# first_light.net
KiCad netlist of a schematic drawn in EAGLE
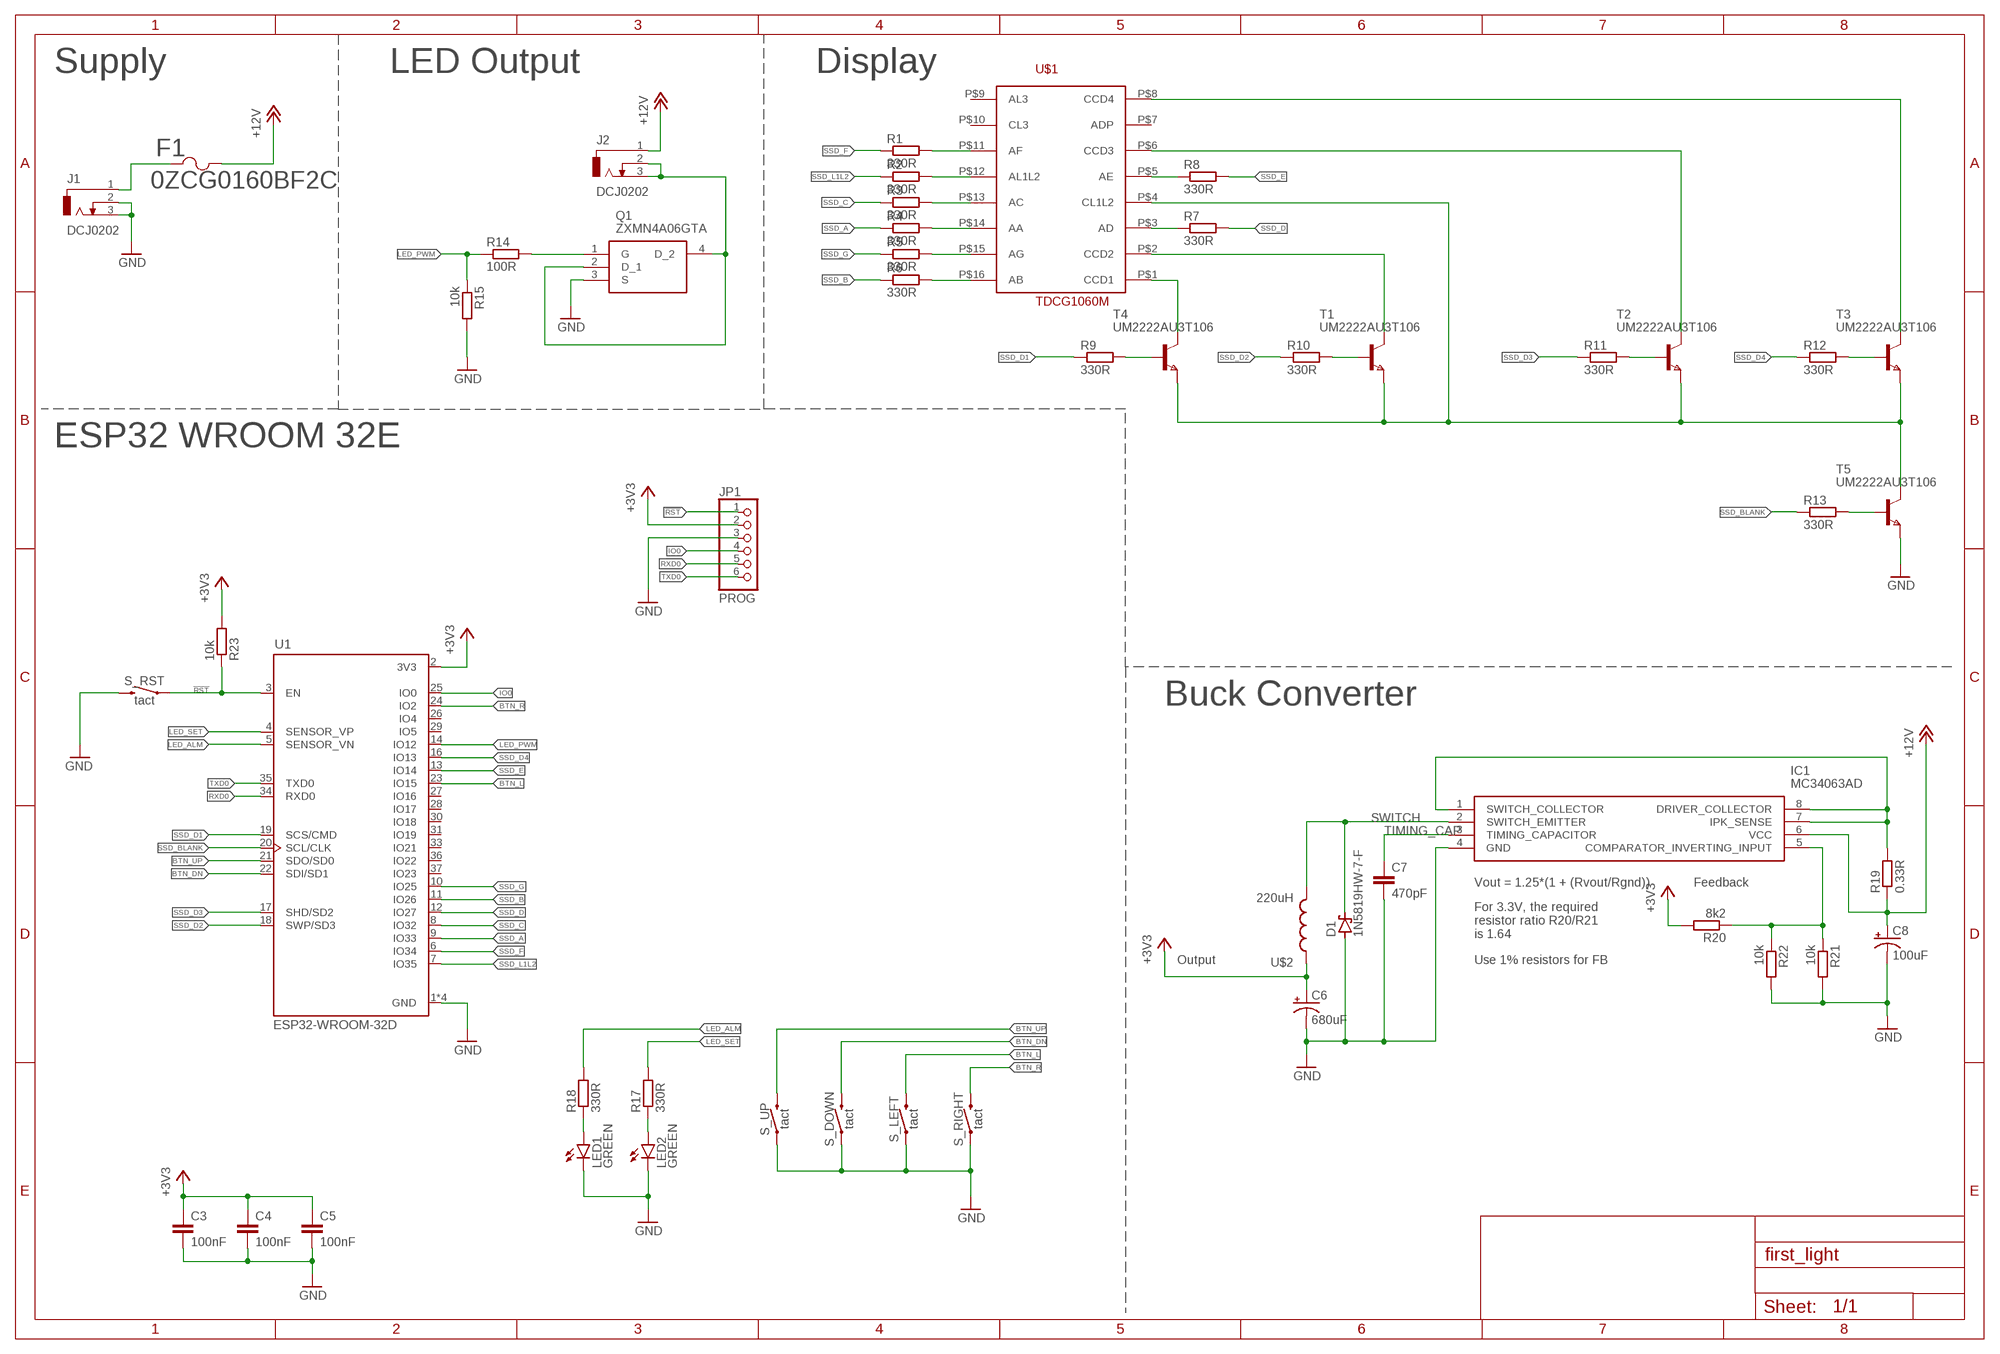
[diagram p0: schematic, sheet 1]

(export (version "E")
  (design (tool "Eeschema 10.0.6"))
  (components
    (comp (ref "C3")
      (value "100nF")
      (footprint "eagle-import:C0603")
      (libsource (lib "eagle-import") (part "C-EUC0603"))
    )
    (comp (ref "C4")
      (value "100nF")
      (footprint "eagle-import:C0603")
      (libsource (lib "eagle-import") (part "C-EUC0603"))
    )
    (comp (ref "C5")
      (value "100nF")
      (footprint "eagle-import:C0603")
      (libsource (lib "eagle-import") (part "C-EUC0603"))
    )
    (comp (ref "C6")
      (value "680uF")
      (footprint "eagle-import:153CLV-0605")
      (libsource (lib "eagle-import") (part "CPOL-US153CLV-0605"))
    )
    (comp (ref "C7")
      (value "470pF")
      (footprint "eagle-import:C0603")
      (libsource (lib "eagle-import") (part "rcl_334_C-EUC0603"))
    )
    (comp (ref "C8")
      (value "100uF")
      (footprint "eagle-import:153CLV-0605")
      (libsource (lib "eagle-import") (part "CPOL-US153CLV-0605"))
    )
    (comp (ref "D1")
      (value "SCHOTTKY-1N5819HW-7-F")
      (footprint "eagle-import:SOD123")
      (libsource (lib "eagle-import") (part "SCHOTTKY-1N5819HW-7-F"))
    )
    (comp (ref "F1")
      (value "0ZCG0160BF2C")
      (footprint "eagle-import:0ZCG_BEL")
      (fields (field (name "COPYRIGHT") "Copyright (C) 2021 Ultra Librarian. All rights reserved."))
      (libsource (lib "eagle-import") (part "0ZCG0160BF2C"))
    )
    (comp (ref "IC1")
      (value "MC34063AD")
      (footprint "eagle-import:SOIC127P600X175-8N")
      (fields (field (name "MOUSER_PART_NUMBER") "512-MC34063AD"))
      (libsource (lib "eagle-import") (part "MC34063AD"))
    )
    (comp (ref "J1")
      (value "DCJ0202")
      (footprint "eagle-import:DCJ0202")
      (libsource (lib "eagle-import") (part "DCJ0202"))
    )
    (comp (ref "J2")
      (value "DCJ0202")
      (footprint "eagle-import:DCJ0202")
      (libsource (lib "eagle-import") (part "DCJ0202"))
    )
    (comp (ref "JP1")
      (value "PROG")
      (footprint "eagle-import:1X06")
      (libsource (lib "eagle-import") (part "PINHD-1X6"))
    )
    (comp (ref "LED1")
      (value "GREEN")
      (footprint "eagle-import:CHIP-LED0603")
      (libsource (lib "eagle-import") (part "LEDCHIP-LED0603"))
    )
    (comp (ref "LED2")
      (value "GREEN")
      (footprint "eagle-import:CHIP-LED0603")
      (libsource (lib "eagle-import") (part "LEDCHIP-LED0603"))
    )
    (comp (ref "Q1")
      (value "ZXMN4A06GTA")
      (footprint "eagle-import:SOT230P700X180-4N")
      (fields (field (name "MOUSER_PART_NUMBER") "522-ZXMN4A06GTA"))
      (libsource (lib "eagle-import") (part "ZXMN4A06GTA"))
    )
    (comp (ref "R1")
      (value "330R")
      (footprint "eagle-import:R0603")
      (libsource (lib "eagle-import") (part "R-EU_R0603"))
    )
    (comp (ref "R2")
      (value "330R")
      (footprint "eagle-import:R0603")
      (libsource (lib "eagle-import") (part "R-EU_R0603"))
    )
    (comp (ref "R3")
      (value "330R")
      (footprint "eagle-import:R0603")
      (libsource (lib "eagle-import") (part "R-EU_R0603"))
    )
    (comp (ref "R4")
      (value "330R")
      (footprint "eagle-import:R0603")
      (libsource (lib "eagle-import") (part "R-EU_R0603"))
    )
    (comp (ref "R5")
      (value "330R")
      (footprint "eagle-import:R0603")
      (libsource (lib "eagle-import") (part "R-EU_R0603"))
    )
    (comp (ref "R6")
      (value "330R")
      (footprint "eagle-import:R0603")
      (libsource (lib "eagle-import") (part "R-EU_R0603"))
    )
    (comp (ref "R7")
      (value "330R")
      (footprint "eagle-import:R0603")
      (libsource (lib "eagle-import") (part "R-EU_R0603"))
    )
    (comp (ref "R8")
      (value "330R")
      (footprint "eagle-import:R0603")
      (libsource (lib "eagle-import") (part "R-EU_R0603"))
    )
    (comp (ref "R9")
      (value "330R")
      (footprint "eagle-import:R0603")
      (libsource (lib "eagle-import") (part "R-EU_R0603"))
    )
    (comp (ref "R10")
      (value "330R")
      (footprint "eagle-import:R0603")
      (libsource (lib "eagle-import") (part "R-EU_R0603"))
    )
    (comp (ref "R11")
      (value "330R")
      (footprint "eagle-import:R0603")
      (libsource (lib "eagle-import") (part "R-EU_R0603"))
    )
    (comp (ref "R12")
      (value "330R")
      (footprint "eagle-import:R0603")
      (libsource (lib "eagle-import") (part "R-EU_R0603"))
    )
    (comp (ref "R13")
      (value "330R")
      (footprint "eagle-import:R0603")
      (libsource (lib "eagle-import") (part "R-EU_R0603"))
    )
    (comp (ref "R14")
      (value "100R")
      (footprint "eagle-import:R0603")
      (libsource (lib "eagle-import") (part "R-EU_R0603"))
    )
    (comp (ref "R15")
      (value "10k")
      (footprint "eagle-import:R0603")
      (libsource (lib "eagle-import") (part "R-EU_R0603"))
    )
    (comp (ref "R17")
      (value "330R")
      (footprint "eagle-import:R0603")
      (libsource (lib "eagle-import") (part "R-EU_R0603"))
    )
    (comp (ref "R18")
      (value "330R")
      (footprint "eagle-import:R0603")
      (libsource (lib "eagle-import") (part "R-EU_R0603"))
    )
    (comp (ref "R19")
      (value "0.33R")
      (footprint "eagle-import:R0603")
      (libsource (lib "eagle-import") (part "R-EU_R0603"))
    )
    (comp (ref "R20")
      (value "8k2")
      (footprint "eagle-import:R0603")
      (libsource (lib "eagle-import") (part "R-EU_R0603"))
    )
    (comp (ref "R21")
      (value "10k")
      (footprint "eagle-import:R0603")
      (libsource (lib "eagle-import") (part "R-EU_R0603"))
    )
    (comp (ref "R22")
      (value "10k")
      (footprint "eagle-import:R0603")
      (libsource (lib "eagle-import") (part "R-EU_R0603"))
    )
    (comp (ref "R23")
      (value "10k")
      (footprint "eagle-import:R0603")
      (libsource (lib "eagle-import") (part "R-EU_R0603"))
    )
    (comp (ref "S_DOWN")
      (value "tact")
      (footprint "eagle-import:TACTILE_SWITCH_PTH_6.0MM")
      (libsource (lib "eagle-import") (part "MOMENTARY-SWITCH-SPST-PTH-6.0MM"))
    )
    (comp (ref "S_LEFT")
      (value "tact")
      (footprint "eagle-import:TACTILE_SWITCH_PTH_6.0MM")
      (libsource (lib "eagle-import") (part "MOMENTARY-SWITCH-SPST-PTH-6.0MM"))
    )
    (comp (ref "S_RIGHT")
      (value "tact")
      (footprint "eagle-import:TACTILE_SWITCH_PTH_6.0MM")
      (libsource (lib "eagle-import") (part "MOMENTARY-SWITCH-SPST-PTH-6.0MM"))
    )
    (comp (ref "S_RST")
      (value "tact")
      (footprint "eagle-import:TACTILE_SWITCH_PTH_6.0MM")
      (libsource (lib "eagle-import") (part "MOMENTARY-SWITCH-SPST-PTH-6.0MM"))
    )
    (comp (ref "S_UP")
      (value "tact")
      (footprint "eagle-import:TACTILE_SWITCH_PTH_6.0MM")
      (libsource (lib "eagle-import") (part "MOMENTARY-SWITCH-SPST-PTH-6.0MM"))
    )
    (comp (ref "T1")
      (value "UM2222AU3T106")
      (footprint "eagle-import:SOT323")
      (fields (field (name "MPN") "DSS4160U-7"))
      (libsource (lib "eagle-import") (part "NPNSOT323"))
    )
    (comp (ref "T2")
      (value "UM2222AU3T106")
      (footprint "eagle-import:SOT323")
      (fields (field (name "MPN") "DSS4160U-7"))
      (libsource (lib "eagle-import") (part "NPNSOT323"))
    )
    (comp (ref "T3")
      (value "UM2222AU3T106")
      (footprint "eagle-import:SOT323")
      (fields (field (name "MPN") "DSS4160U-7"))
      (libsource (lib "eagle-import") (part "NPNSOT323"))
    )
    (comp (ref "T4")
      (value "UM2222AU3T106")
      (footprint "eagle-import:SOT323")
      (fields (field (name "MPN") "DSS4160U-7"))
      (libsource (lib "eagle-import") (part "NPNSOT323"))
    )
    (comp (ref "T5")
      (value "UM2222AU3T106")
      (footprint "eagle-import:SOT323")
      (fields (field (name "MPN") "DSS4160U-7"))
      (libsource (lib "eagle-import") (part "NPNSOT323"))
    )
    (comp (ref "U$1")
      (value "TDCG1060M")
      (footprint "eagle-import:TDCG1060M")
      (libsource (lib "eagle-import") (part "TDCG1060M"))
    )
    (comp (ref "U$2")
      (value "220uH")
      (footprint "eagle-import:1010_INDUCTOR")
      (libsource (lib "eagle-import") (part "1010_INDUCTOR"))
    )
    (comp (ref "U1")
      (value "ESP32-WROOM-32D")
      (footprint "eagle-import:MODULE_ESP32-WROOM-32D")
      (fields (field (name "MF") "Espressif Systems"))
      (libsource (lib "eagle-import") (part "ESP32-WROOM-32D"))
    )
  )
  (nets
    (net (code "1") (name "+3V3") (class "Default")
      (node (ref "C3") (pin "1") (pinfunction "1_1") (pintype "passive"))
      (node (ref "C4") (pin "1") (pinfunction "1_1") (pintype "passive"))
      (node (ref "C5") (pin "1") (pinfunction "1_1") (pintype "passive"))
      (node (ref "C6") (pin "+") (pinfunction "+_+") (pintype "passive"))
      (node (ref "JP1") (pin "2") (pinfunction "2_2") (pintype "passive"))
      (node (ref "R20") (pin "2") (pinfunction "2_2") (pintype "passive"))
      (node (ref "R23") (pin "2") (pinfunction "2_2") (pintype "passive"))
      (node (ref "U$2") (pin "1") (pinfunction "1_1") (pintype "passive"))
      (node (ref "U1") (pin "2") (pinfunction "3V3_2") (pintype "power_in"))
    )
    (net (code "2") (name "+12V") (class "Default")
      (node (ref "C8") (pin "+") (pinfunction "+_+") (pintype "passive"))
      (node (ref "F1") (pin "2") (pinfunction "2_2") (pintype "passive"))
      (node (ref "IC1") (pin "6") (pinfunction "VCC_6") (pintype "bidirectional"))
      (node (ref "J2") (pin "1") (pinfunction "1_1") (pintype "passive"))
      (node (ref "R19") (pin "1") (pinfunction "1_1") (pintype "passive"))
    )
    (net (code "3") (name "/SWITCH") (class "Default")
      (node (ref "D1") (pin "1") (pinfunction "C_1") (pintype "passive"))
      (node (ref "IC1") (pin "2") (pinfunction "SWITCH_EMITTER_2") (pintype "bidirectional"))
      (node (ref "U$2") (pin "2") (pinfunction "2_2") (pintype "passive"))
    )
    (net (code "4") (name "/TIMING_CAP") (class "Default")
      (node (ref "C7") (pin "1") (pinfunction "1_1") (pintype "passive"))
      (node (ref "IC1") (pin "3") (pinfunction "TIMING_CAPACITOR_3") (pintype "bidirectional"))
    )
    (net (code "5") (name "/~{RST}") (class "Default")
      (node (ref "JP1") (pin "1") (pinfunction "1_1") (pintype "passive"))
      (node (ref "R23") (pin "1") (pinfunction "1_1") (pintype "passive"))
      (node (ref "S_RST") (pin "1") (pinfunction "1_1") (pintype "passive"))
      (node (ref "U1") (pin "3") (pinfunction "EN_3") (pintype "input"))
    )
    (net (code "6") (name "BTN_DN") (class "Default")
      (node (ref "S_DOWN") (pin "3") (pinfunction "2_3") (pintype "passive"))
      (node (ref "U1") (pin "22") (pinfunction "SDI/SD1_22") (pintype "bidirectional"))
    )
    (net (code "7") (name "BTN_L") (class "Default")
      (node (ref "S_LEFT") (pin "3") (pinfunction "2_3") (pintype "passive"))
      (node (ref "U1") (pin "23") (pinfunction "IO15_23") (pintype "bidirectional"))
    )
    (net (code "8") (name "BTN_R") (class "Default")
      (node (ref "S_RIGHT") (pin "3") (pinfunction "2_3") (pintype "passive"))
      (node (ref "U1") (pin "24") (pinfunction "IO2_24") (pintype "bidirectional"))
    )
    (net (code "9") (name "BTN_UP") (class "Default")
      (node (ref "S_UP") (pin "3") (pinfunction "2_3") (pintype "passive"))
      (node (ref "U1") (pin "21") (pinfunction "SDO/SD0_21") (pintype "bidirectional"))
    )
    (net (code "10") (name "GND") (class "Default")
      (node (ref "C3") (pin "2") (pinfunction "2_2") (pintype "passive"))
      (node (ref "C4") (pin "2") (pinfunction "2_2") (pintype "passive"))
      (node (ref "C5") (pin "2") (pinfunction "2_2") (pintype "passive"))
      (node (ref "C6") (pin "-") (pinfunction "-_-") (pintype "passive"))
      (node (ref "C7") (pin "2") (pinfunction "2_2") (pintype "passive"))
      (node (ref "C8") (pin "-") (pinfunction "-_-") (pintype "passive"))
      (node (ref "D1") (pin "2") (pinfunction "A_2") (pintype "passive"))
      (node (ref "IC1") (pin "4") (pinfunction "GND_4") (pintype "bidirectional"))
      (node (ref "J1") (pin "2") (pinfunction "2_2") (pintype "passive"))
      (node (ref "J1") (pin "3") (pinfunction "3_3") (pintype "passive"))
      (node (ref "JP1") (pin "3") (pinfunction "3_3") (pintype "passive"))
      (node (ref "LED1") (pin "C") (pinfunction "C_C") (pintype "passive"))
      (node (ref "LED2") (pin "C") (pinfunction "C_C") (pintype "passive"))
      (node (ref "Q1") (pin "3") (pinfunction "S_3") (pintype "bidirectional"))
      (node (ref "R15") (pin "2") (pinfunction "2_2") (pintype "passive"))
      (node (ref "R21") (pin "2") (pinfunction "2_2") (pintype "passive"))
      (node (ref "R22") (pin "2") (pinfunction "2_2") (pintype "passive"))
      (node (ref "S_DOWN") (pin "1") (pinfunction "1_1") (pintype "passive"))
      (node (ref "S_LEFT") (pin "1") (pinfunction "1_1") (pintype "passive"))
      (node (ref "S_RIGHT") (pin "1") (pinfunction "1_1") (pintype "passive"))
      (node (ref "S_RST") (pin "3") (pinfunction "2_3") (pintype "passive"))
      (node (ref "S_UP") (pin "1") (pinfunction "1_1") (pintype "passive"))
      (node (ref "T5") (pin "3") (pinfunction "E_3") (pintype "passive"))
      (node (ref "U1") (pin "1") (pinfunction "GND_1") (pintype "power_in"))
      (node (ref "U1") (pin "15") (pinfunction "GND_15") (pintype "power_in"))
      (node (ref "U1") (pin "38") (pinfunction "GND_38") (pintype "power_in"))
      (node (ref "U1") (pin "39") (pinfunction "GND_39") (pintype "power_in"))
    )
    (net (code "11") (name "IO0") (class "Default")
      (node (ref "JP1") (pin "4") (pinfunction "4_4") (pintype "passive"))
      (node (ref "U1") (pin "25") (pinfunction "IO0_25") (pintype "bidirectional"))
    )
    (net (code "12") (name "LED_ALM") (class "Default")
      (node (ref "R18") (pin "2") (pinfunction "2_2") (pintype "passive"))
      (node (ref "U1") (pin "5") (pinfunction "SENSOR_VN_5") (pintype "input"))
    )
    (net (code "13") (name "LED_PWM") (class "Default")
      (node (ref "R14") (pin "1") (pinfunction "1_1") (pintype "passive"))
      (node (ref "R15") (pin "1") (pinfunction "1_1") (pintype "passive"))
      (node (ref "U1") (pin "14") (pinfunction "IO12_14") (pintype "bidirectional"))
    )
    (net (code "14") (name "LED_SET") (class "Default")
      (node (ref "R17") (pin "2") (pinfunction "2_2") (pintype "passive"))
      (node (ref "U1") (pin "4") (pinfunction "SENSOR_VP_4") (pintype "input"))
    )
    (net (code "15") (name "Net-(F1-Pad1)") (class "Default")
      (node (ref "F1") (pin "1") (pinfunction "1_1") (pintype "passive"))
      (node (ref "J1") (pin "1") (pinfunction "1_1") (pintype "passive"))
    )
    (net (code "16") (name "Net-(IC1-COMPARATOR_INVERTING_INPUT)") (class "Default")
      (node (ref "IC1") (pin "5") (pinfunction "COMPARATOR_INVERTING_INPUT_5") (pintype "bidirectional"))
      (node (ref "R20") (pin "1") (pinfunction "1_1") (pintype "passive"))
      (node (ref "R21") (pin "1") (pinfunction "1_1") (pintype "passive"))
      (node (ref "R22") (pin "1") (pinfunction "1_1") (pintype "passive"))
    )
    (net (code "17") (name "Net-(IC1-DRIVER_COLLECTOR)") (class "Default")
      (node (ref "IC1") (pin "1") (pinfunction "SWITCH_COLLECTOR_1") (pintype "bidirectional"))
      (node (ref "IC1") (pin "7") (pinfunction "IPK_SENSE_7") (pintype "bidirectional"))
      (node (ref "IC1") (pin "8") (pinfunction "DRIVER_COLLECTOR_8") (pintype "bidirectional"))
      (node (ref "R19") (pin "2") (pinfunction "2_2") (pintype "passive"))
    )
    (net (code "18") (name "Net-(LED1-PadA)") (class "Default")
      (node (ref "LED1") (pin "A") (pinfunction "A_A") (pintype "passive"))
      (node (ref "R18") (pin "1") (pinfunction "1_1") (pintype "passive"))
    )
    (net (code "19") (name "Net-(LED2-PadA)") (class "Default")
      (node (ref "LED2") (pin "A") (pinfunction "A_A") (pintype "passive"))
      (node (ref "R17") (pin "1") (pinfunction "1_1") (pintype "passive"))
    )
    (net (code "20") (name "Net-(Q1-D_1)") (class "Default")
      (node (ref "J2") (pin "2") (pinfunction "2_2") (pintype "passive"))
      (node (ref "J2") (pin "3") (pinfunction "3_3") (pintype "passive"))
      (node (ref "Q1") (pin "2") (pinfunction "D_1_2") (pintype "bidirectional"))
      (node (ref "Q1") (pin "4") (pinfunction "D_2_4") (pintype "bidirectional"))
    )
    (net (code "21") (name "Net-(Q1-G)") (class "Default")
      (node (ref "Q1") (pin "1") (pinfunction "G_1") (pintype "bidirectional"))
      (node (ref "R14") (pin "2") (pinfunction "2_2") (pintype "passive"))
    )
    (net (code "22") (name "Net-(T1-B)") (class "Default")
      (node (ref "R10") (pin "2") (pinfunction "2_2") (pintype "passive"))
      (node (ref "T1") (pin "2") (pinfunction "B_2") (pintype "passive"))
    )
    (net (code "23") (name "Net-(T1-C)") (class "Default")
      (node (ref "T1") (pin "1") (pinfunction "C_1") (pintype "passive"))
      (node (ref "U$1") (pin "P$2") (pinfunction "CCD2_P$2") (pintype "bidirectional"))
    )
    (net (code "24") (name "Net-(T1-E)") (class "Default")
      (node (ref "T1") (pin "3") (pinfunction "E_3") (pintype "passive"))
      (node (ref "T2") (pin "3") (pinfunction "E_3") (pintype "passive"))
      (node (ref "T3") (pin "3") (pinfunction "E_3") (pintype "passive"))
      (node (ref "T4") (pin "3") (pinfunction "E_3") (pintype "passive"))
      (node (ref "T5") (pin "1") (pinfunction "C_1") (pintype "passive"))
      (node (ref "U$1") (pin "P$4") (pinfunction "CL1L2_P$4") (pintype "bidirectional"))
    )
    (net (code "25") (name "Net-(T2-B)") (class "Default")
      (node (ref "R11") (pin "2") (pinfunction "2_2") (pintype "passive"))
      (node (ref "T2") (pin "2") (pinfunction "B_2") (pintype "passive"))
    )
    (net (code "26") (name "Net-(T2-C)") (class "Default")
      (node (ref "T2") (pin "1") (pinfunction "C_1") (pintype "passive"))
      (node (ref "U$1") (pin "P$6") (pinfunction "CCD3_P$6") (pintype "bidirectional"))
    )
    (net (code "27") (name "Net-(T3-B)") (class "Default")
      (node (ref "R12") (pin "2") (pinfunction "2_2") (pintype "passive"))
      (node (ref "T3") (pin "2") (pinfunction "B_2") (pintype "passive"))
    )
    (net (code "28") (name "Net-(T3-C)") (class "Default")
      (node (ref "T3") (pin "1") (pinfunction "C_1") (pintype "passive"))
      (node (ref "U$1") (pin "P$8") (pinfunction "CCD4_P$8") (pintype "bidirectional"))
    )
    (net (code "29") (name "Net-(T4-B)") (class "Default")
      (node (ref "R9") (pin "2") (pinfunction "2_2") (pintype "passive"))
      (node (ref "T4") (pin "2") (pinfunction "B_2") (pintype "passive"))
    )
    (net (code "30") (name "Net-(T4-C)") (class "Default")
      (node (ref "T4") (pin "1") (pinfunction "C_1") (pintype "passive"))
      (node (ref "U$1") (pin "P$1") (pinfunction "CCD1_P$1") (pintype "bidirectional"))
    )
    (net (code "31") (name "Net-(T5-B)") (class "Default")
      (node (ref "R13") (pin "2") (pinfunction "2_2") (pintype "passive"))
      (node (ref "T5") (pin "2") (pinfunction "B_2") (pintype "passive"))
    )
    (net (code "32") (name "Net-(U$1-AA)") (class "Default")
      (node (ref "R4") (pin "2") (pinfunction "2_2") (pintype "passive"))
      (node (ref "U$1") (pin "P$14") (pinfunction "AA_P$14") (pintype "bidirectional"))
    )
    (net (code "33") (name "Net-(U$1-AB)") (class "Default")
      (node (ref "R6") (pin "2") (pinfunction "2_2") (pintype "passive"))
      (node (ref "U$1") (pin "P$16") (pinfunction "AB_P$16") (pintype "bidirectional"))
    )
    (net (code "34") (name "Net-(U$1-AC)") (class "Default")
      (node (ref "R3") (pin "2") (pinfunction "2_2") (pintype "passive"))
      (node (ref "U$1") (pin "P$13") (pinfunction "AC_P$13") (pintype "bidirectional"))
    )
    (net (code "35") (name "Net-(U$1-AD)") (class "Default")
      (node (ref "R7") (pin "1") (pinfunction "1_1") (pintype "passive"))
      (node (ref "U$1") (pin "P$3") (pinfunction "AD_P$3") (pintype "bidirectional"))
    )
    (net (code "36") (name "Net-(U$1-AE)") (class "Default")
      (node (ref "R8") (pin "1") (pinfunction "1_1") (pintype "passive"))
      (node (ref "U$1") (pin "P$5") (pinfunction "AE_P$5") (pintype "bidirectional"))
    )
    (net (code "37") (name "Net-(U$1-AF)") (class "Default")
      (node (ref "R1") (pin "2") (pinfunction "2_2") (pintype "passive"))
      (node (ref "U$1") (pin "P$11") (pinfunction "AF_P$11") (pintype "bidirectional"))
    )
    (net (code "38") (name "Net-(U$1-AG)") (class "Default")
      (node (ref "R5") (pin "2") (pinfunction "2_2") (pintype "passive"))
      (node (ref "U$1") (pin "P$15") (pinfunction "AG_P$15") (pintype "bidirectional"))
    )
    (net (code "39") (name "Net-(U$1-AL1L2)") (class "Default")
      (node (ref "R2") (pin "2") (pinfunction "2_2") (pintype "passive"))
      (node (ref "U$1") (pin "P$12") (pinfunction "AL1L2_P$12") (pintype "bidirectional"))
    )
    (net (code "40") (name "RXD0") (class "Default")
      (node (ref "JP1") (pin "5") (pinfunction "5_5") (pintype "passive"))
      (node (ref "U1") (pin "34") (pinfunction "RXD0_34") (pintype "bidirectional"))
    )
    (net (code "41") (name "SSD_A") (class "Default")
      (node (ref "R4") (pin "1") (pinfunction "1_1") (pintype "passive"))
      (node (ref "U1") (pin "9") (pinfunction "IO33_9") (pintype "bidirectional"))
    )
    (net (code "42") (name "SSD_B") (class "Default")
      (node (ref "R6") (pin "1") (pinfunction "1_1") (pintype "passive"))
      (node (ref "U1") (pin "11") (pinfunction "IO26_11") (pintype "bidirectional"))
    )
    (net (code "43") (name "SSD_BLANK") (class "Default")
      (node (ref "R13") (pin "1") (pinfunction "1_1") (pintype "passive"))
      (node (ref "U1") (pin "20") (pinfunction "SCL/CLK_20") (pintype "bidirectional"))
    )
    (net (code "44") (name "SSD_C") (class "Default")
      (node (ref "R3") (pin "1") (pinfunction "1_1") (pintype "passive"))
      (node (ref "U1") (pin "8") (pinfunction "IO32_8") (pintype "bidirectional"))
    )
    (net (code "45") (name "SSD_D") (class "Default")
      (node (ref "R7") (pin "2") (pinfunction "2_2") (pintype "passive"))
      (node (ref "U1") (pin "12") (pinfunction "IO27_12") (pintype "bidirectional"))
    )
    (net (code "46") (name "SSD_D1") (class "Default")
      (node (ref "R9") (pin "1") (pinfunction "1_1") (pintype "passive"))
      (node (ref "U1") (pin "19") (pinfunction "SCS/CMD_19") (pintype "bidirectional"))
    )
    (net (code "47") (name "SSD_D2") (class "Default")
      (node (ref "R10") (pin "1") (pinfunction "1_1") (pintype "passive"))
      (node (ref "U1") (pin "18") (pinfunction "SWP/SD3_18") (pintype "bidirectional"))
    )
    (net (code "48") (name "SSD_D3") (class "Default")
      (node (ref "R11") (pin "1") (pinfunction "1_1") (pintype "passive"))
      (node (ref "U1") (pin "17") (pinfunction "SHD/SD2_17") (pintype "bidirectional"))
    )
    (net (code "49") (name "SSD_D4") (class "Default")
      (node (ref "R12") (pin "1") (pinfunction "1_1") (pintype "passive"))
      (node (ref "U1") (pin "16") (pinfunction "IO13_16") (pintype "bidirectional"))
    )
    (net (code "50") (name "SSD_E") (class "Default")
      (node (ref "R8") (pin "2") (pinfunction "2_2") (pintype "passive"))
      (node (ref "U1") (pin "13") (pinfunction "IO14_13") (pintype "bidirectional"))
    )
    (net (code "51") (name "SSD_F") (class "Default")
      (node (ref "R1") (pin "1") (pinfunction "1_1") (pintype "passive"))
      (node (ref "U1") (pin "6") (pinfunction "IO34_6") (pintype "bidirectional"))
    )
    (net (code "52") (name "SSD_G") (class "Default")
      (node (ref "R5") (pin "1") (pinfunction "1_1") (pintype "passive"))
      (node (ref "U1") (pin "10") (pinfunction "IO25_10") (pintype "bidirectional"))
    )
    (net (code "53") (name "SSD_L1L2") (class "Default")
      (node (ref "R2") (pin "1") (pinfunction "1_1") (pintype "passive"))
      (node (ref "U1") (pin "7") (pinfunction "IO35_7") (pintype "bidirectional"))
    )
    (net (code "54") (name "TXD0") (class "Default")
      (node (ref "JP1") (pin "6") (pinfunction "6_6") (pintype "passive"))
      (node (ref "U1") (pin "35") (pinfunction "TXD0_35") (pintype "bidirectional"))
    )
    (net (code "55") (name "unconnected-(U$1-ADP-PadP$7)") (class "Default")
      (node (ref "U$1") (pin "P$7") (pinfunction "ADP_P$7") (pintype "bidirectional"))
    )
    (net (code "56") (name "unconnected-(U$1-AL3-PadP$9)") (class "Default")
      (node (ref "U$1") (pin "P$9") (pinfunction "AL3_P$9") (pintype "bidirectional"))
    )
    (net (code "57") (name "unconnected-(U$1-CL3-PadP$10)") (class "Default")
      (node (ref "U$1") (pin "P$10") (pinfunction "CL3_P$10") (pintype "bidirectional"))
    )
    (net (code "58") (name "unconnected-(U1-IO4-Pad26)") (class "Default")
      (node (ref "U1") (pin "26") (pinfunction "IO4_26") (pintype "bidirectional"))
    )
    (net (code "59") (name "unconnected-(U1-IO5-Pad29)") (class "Default")
      (node (ref "U1") (pin "29") (pinfunction "IO5_29") (pintype "bidirectional"))
    )
    (net (code "60") (name "unconnected-(U1-IO16-Pad27)") (class "Default")
      (node (ref "U1") (pin "27") (pinfunction "IO16_27") (pintype "bidirectional"))
    )
    (net (code "61") (name "unconnected-(U1-IO17-Pad28)") (class "Default")
      (node (ref "U1") (pin "28") (pinfunction "IO17_28") (pintype "bidirectional"))
    )
    (net (code "62") (name "unconnected-(U1-IO18-Pad30)") (class "Default")
      (node (ref "U1") (pin "30") (pinfunction "IO18_30") (pintype "bidirectional"))
    )
    (net (code "63") (name "unconnected-(U1-IO19-Pad31)") (class "Default")
      (node (ref "U1") (pin "31") (pinfunction "IO19_31") (pintype "bidirectional"))
    )
    (net (code "64") (name "unconnected-(U1-IO21-Pad33)") (class "Default")
      (node (ref "U1") (pin "33") (pinfunction "IO21_33") (pintype "bidirectional"))
    )
    (net (code "65") (name "unconnected-(U1-IO22-Pad36)") (class "Default")
      (node (ref "U1") (pin "36") (pinfunction "IO22_36") (pintype "bidirectional"))
    )
    (net (code "66") (name "unconnected-(U1-IO23-Pad37)") (class "Default")
      (node (ref "U1") (pin "37") (pinfunction "IO23_37") (pintype "bidirectional"))
    )
  )
)
